# USB_PD.net
KiCad netlist of a schematic drawn in Altium Designer
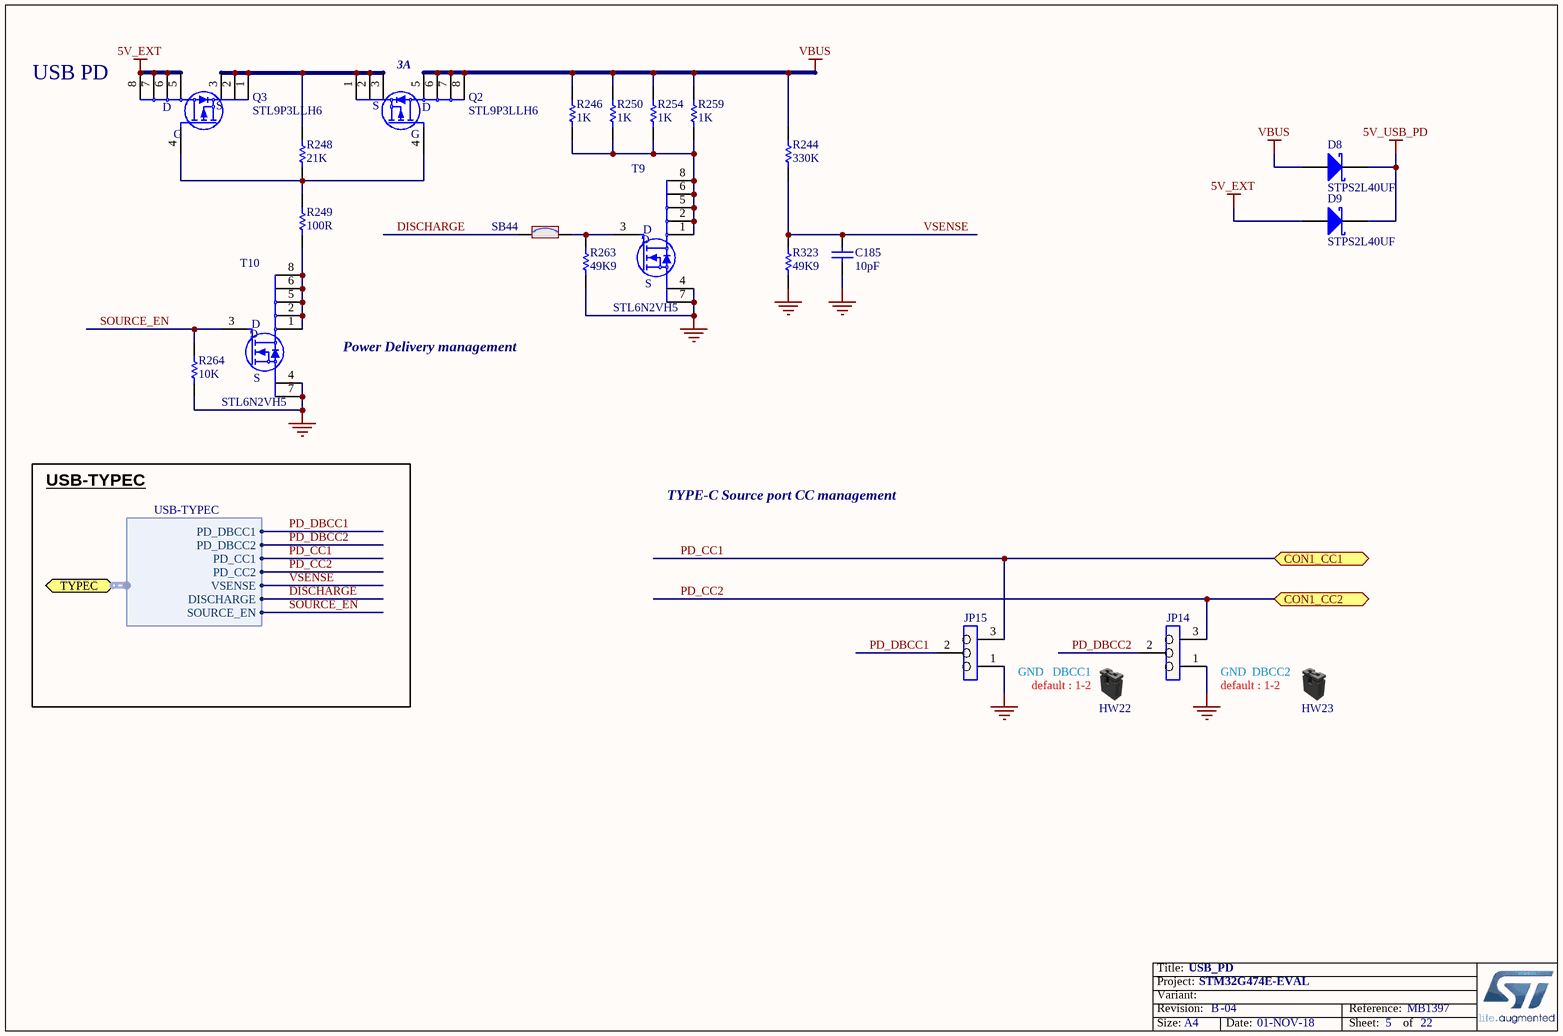
[diagram p0: USB_PD.SchDoc]

(export (version "E")
  (design (tool "Eeschema 10.0.6"))
  (components
    (comp (ref "C185")
      (value "10pF")
      (footprint "C0603")
      (description "Capacitor, MLCC, 10pF, 50V, NPO, 5%, 0603, T=0,8mm")
      (fields
        (field (name "INTERNAL_PART_NUMBER") "MCD-00637")
        (field (name "MANUFACTURER_PART_NUMBER") "CC0603JRNPO9BN100")
        (field (name "PROVIDED_BY") "SUBCO")
      )
      (libsource (lib "MCD_PARTS_database") (part "Capacitor"))
    )
    (comp (ref "D8")
      (value "STPS2L40UF")
      (footprint "DIO_SMB-FLAT_1A_2K")
      (description "Low drop power Schottky rectifier(2A, 40V, 0.34V)")
      (fields
        (field (name "INTERNAL_PART_NUMBER") "MCD-01087")
        (field (name "MANUFACTURER") "STMICROELECTRONICS")
        (field (name "PROVIDED_BY") "SUBCO with ST control")
      )
      (libsource (lib "MCD_PARTS_database") (part "STPS2L40UF"))
    )
    (comp (ref "D9")
      (value "STPS2L40UF")
      (footprint "DIO_SMB-FLAT_1A_2K")
      (description "Low drop power Schottky rectifier(2A, 40V, 0.34V)")
      (fields
        (field (name "INTERNAL_PART_NUMBER") "MCD-01087")
        (field (name "MANUFACTURER") "STMICROELECTRONICS")
        (field (name "PROVIDED_BY") "SUBCO with ST control")
      )
      (libsource (lib "MCD_PARTS_database") (part "STPS2L40UF"))
    )
    (comp (ref "HW22")
      (value "Shunt Black 2.54mm")
      (description "SHUNT 2.54mm BLACK")
      (fields
        (field (name "INTERNAL_PART_NUMBER") "MCD-00043")
        (field (name "MANUFACTURER_PART_NUMBER") "SNT-100-BK-G")
        (field (name "PROVIDED_BY") "SUBCO")
      )
      (libsource (lib "MCD_PARTS_database") (part "Shunt Black 2.54mm"))
    )
    (comp (ref "HW23")
      (value "Shunt Black 2.54mm")
      (description "SHUNT 2.54mm BLACK")
      (fields
        (field (name "INTERNAL_PART_NUMBER") "MCD-00043")
        (field (name "MANUFACTURER_PART_NUMBER") "SNT-100-BK-G")
        (field (name "PROVIDED_BY") "SUBCO")
      )
      (libsource (lib "MCD_PARTS_database") (part "Shunt Black 2.54mm"))
    )
    (comp (ref "JP14")
      (value "Jumper_Header 3x1")
      (footprint "CON_SAMTEC_TSW-103-07-F-S")
      (description "Header, 3x1, 2,54mm, VR, TH, Height 5.84mm/2.54mm")
      (fields
        (field (name "INTERNAL_PART_NUMBER") "MCD-00111")
        (field (name "MANUFACTURER_PART_NUMBER") "TSW-103-07-F-S")
        (field (name "PROVIDED_BY") "SUBCO")
      )
      (libsource (lib "MCD_PARTS_database") (part "Jumper_Header 3x1"))
    )
    (comp (ref "JP15")
      (value "Jumper_Header 3x1")
      (footprint "CON_SAMTEC_TSW-103-07-F-S")
      (description "Header, 3x1, 2,54mm, VR, TH, Height 5.84mm/2.54mm")
      (fields
        (field (name "INTERNAL_PART_NUMBER") "MCD-00111")
        (field (name "MANUFACTURER_PART_NUMBER") "TSW-103-07-F-S")
        (field (name "PROVIDED_BY") "SUBCO")
      )
      (libsource (lib "MCD_PARTS_database") (part "Jumper_Header 3x1"))
    )
    (comp (ref "Q2")
      (value "STL9P3LLH6")
      (footprint "MOS_POWERFLAT_3P3X3P3_P065")
      (description "Power Mosfet, P-channel,VDS -30V,RDS 12mohm typ,ID -9A")
      (fields
        (field (name "INTERNAL_PART_NUMBER") "MCD-01126")
        (field (name "MANUFACTURER") "STMICROELECTRONICS")
        (field (name "PROVIDED_BY") "SUBCO with ST control")
      )
      (libsource (lib "MCD_PARTS_database") (part "STL9P3LLH6"))
    )
    (comp (ref "Q3")
      (value "STL9P3LLH6")
      (footprint "MOS_POWERFLAT_3P3X3P3_P065")
      (description "Power Mosfet, P-channel,VDS -30V,RDS 12mohm typ,ID -9A")
      (fields
        (field (name "INTERNAL_PART_NUMBER") "MCD-01126")
        (field (name "MANUFACTURER") "STMICROELECTRONICS")
        (field (name "PROVIDED_BY") "SUBCO with ST control")
      )
      (libsource (lib "MCD_PARTS_database") (part "STL9P3LLH6"))
    )
    (comp (ref "R244")
      (value "330K")
      (footprint "R0603")
      (description "Resistor,330K,0603,1%,1/10W")
      (fields
        (field (name "INTERNAL_PART_NUMBER") "MCD-00458")
        (field (name "MANUFACTURER_PART_NUMBER") "RC0603FR-07330KL")
        (field (name "PROVIDED_BY") "SUBCO")
      )
      (libsource (lib "MCD_PARTS_database") (part "Resistor"))
    )
    (comp (ref "R246")
      (value "1K")
      (footprint "R0603")
      (description "Resistor,1K,0603,1%,1/10W")
      (fields
        (field (name "INTERNAL_PART_NUMBER") "MCD-00070")
        (field (name "MANUFACTURER_PART_NUMBER") "RC0603FR-071KL")
        (field (name "PROVIDED_BY") "SUBCO")
      )
      (libsource (lib "MCD_PARTS_database") (part "Resistor"))
    )
    (comp (ref "R248")
      (value "21K")
      (footprint "R0603")
      (description "Resistor,21K,0603,1%,1/10W")
      (fields
        (field (name "INTERNAL_PART_NUMBER") "MCD-01189")
        (field (name "MANUFACTURER_PART_NUMBER") "RC0603FR-0721KL")
        (field (name "PROVIDED_BY") "SUBCO")
      )
      (libsource (lib "MCD_PARTS_database") (part "Resistor"))
    )
    (comp (ref "R249")
      (value "100R")
      (footprint "R0603")
      (description "Resistor,100R,0603,1%,1/10W")
      (fields
        (field (name "INTERNAL_PART_NUMBER") "MCD-00224")
        (field (name "MANUFACTURER_PART_NUMBER") "RC0603FR-07100RL")
        (field (name "PROVIDED_BY") "SUBCO")
      )
      (libsource (lib "MCD_PARTS_database") (part "Resistor"))
    )
    (comp (ref "R250")
      (value "1K")
      (footprint "R0603")
      (description "Resistor,1K,0603,1%,1/10W")
      (fields
        (field (name "INTERNAL_PART_NUMBER") "MCD-00070")
        (field (name "MANUFACTURER_PART_NUMBER") "RC0603FR-071KL")
        (field (name "PROVIDED_BY") "SUBCO")
      )
      (libsource (lib "MCD_PARTS_database") (part "Resistor"))
    )
    (comp (ref "R254")
      (value "1K")
      (footprint "R0603")
      (description "Resistor,1K,0603,1%,1/10W")
      (fields
        (field (name "INTERNAL_PART_NUMBER") "MCD-00070")
        (field (name "MANUFACTURER_PART_NUMBER") "RC0603FR-071KL")
        (field (name "PROVIDED_BY") "SUBCO")
      )
      (libsource (lib "MCD_PARTS_database") (part "Resistor"))
    )
    (comp (ref "R259")
      (value "1K")
      (footprint "R0603")
      (description "Resistor,1K,0603,1%,1/10W")
      (fields
        (field (name "INTERNAL_PART_NUMBER") "MCD-00070")
        (field (name "MANUFACTURER_PART_NUMBER") "RC0603FR-071KL")
        (field (name "PROVIDED_BY") "SUBCO")
      )
      (libsource (lib "MCD_PARTS_database") (part "Resistor"))
    )
    (comp (ref "R263")
      (value "49K9")
      (footprint "R0603")
      (description "Resistor,49K9,0603,1%")
      (fields
        (field (name "INTERNAL_PART_NUMBER") "MCD-01171")
        (field (name "MANUFACTURER_PART_NUMBER") "RC0603FR-0749K9L")
        (field (name "PROVIDED_BY") "SUBCO")
      )
      (libsource (lib "MCD_PARTS_database") (part "Resistor"))
    )
    (comp (ref "R264")
      (value "10K")
      (footprint "R0603")
      (description "Resistor,10K,0603,1%,1/10W")
      (fields
        (field (name "INTERNAL_PART_NUMBER") "MCD-00220")
        (field (name "MANUFACTURER_PART_NUMBER") "RC0603FR-0710KL")
        (field (name "PROVIDED_BY") "SUBCO")
      )
      (libsource (lib "MCD_PARTS_database") (part "Resistor"))
    )
    (comp (ref "R323")
      (value "49K9")
      (footprint "R0603")
      (description "Resistor,49K9,0603,1%")
      (fields
        (field (name "INTERNAL_PART_NUMBER") "MCD-01171")
        (field (name "MANUFACTURER_PART_NUMBER") "RC0603FR-0749K9L")
        (field (name "PROVIDED_BY") "SUBCO")
      )
      (libsource (lib "MCD_PARTS_database") (part "Resistor"))
    )
    (comp (ref "SB44")
      (value "SB_ON")
      (footprint "SOLDER-BRIDGE_R0603-0R")
      (description "Solder Bridge ON")
      (fields
        (field (name "INTERNAL_PART_NUMBER") "MCD-00071")
        (field (name "MANUFACTURER_PART_NUMBER") "RC0603JR-070RL")
        (field (name "PROVIDED_BY") "SUBCO")
      )
      (libsource (lib "MCD_PARTS_database") (part "SB_ON"))
    )
    (comp (ref "T9")
      (value "STL6N2VH5")
      (footprint "MOS_POWERFLAT_2X2_P065")
      (description "N-channel 20 V, 0.025 O typ., 6 A STripFET™ V Power MOSFET in a PowerFLAT™ 2x2 package")
      (fields
        (field (name "INTERNAL_PART_NUMBER") "MCD-01028")
        (field (name "MANUFACTURER") "STMICROELECTRONICS")
        (field (name "PROVIDED_BY") "SUBCO with ST control")
      )
      (libsource (lib "MCD_PARTS_database") (part "STL6N2VH5"))
    )
    (comp (ref "T10")
      (value "STL6N2VH5")
      (footprint "MOS_POWERFLAT_2X2_P065")
      (description "N-channel 20 V, 0.025 O typ., 6 A STripFET™ V Power MOSFET in a PowerFLAT™ 2x2 package")
      (fields
        (field (name "INTERNAL_PART_NUMBER") "MCD-01028")
        (field (name "MANUFACTURER") "STMICROELECTRONICS")
        (field (name "PROVIDED_BY") "SUBCO with ST control")
      )
      (libsource (lib "MCD_PARTS_database") (part "STL6N2VH5"))
    )
  )
  (nets
    (net (code "2") (name "/DISCHARGE") (class "Default")
      (node (ref "SB44") (pin "1") (pinfunction "1_1") (pintype "passive"))
    )
    (net (code "3") (name "/PD_CC1") (class "Default")
      (node (ref "JP15") (pin "3") (pinfunction "3_3") (pintype "passive"))
    )
    (net (code "4") (name "/PD_CC2") (class "Default")
      (node (ref "JP14") (pin "3") (pinfunction "3_3") (pintype "passive"))
    )
    (net (code "5") (name "/PD_DBCC1") (class "Default")
      (node (ref "JP15") (pin "2") (pinfunction "2_2") (pintype "passive"))
    )
    (net (code "6") (name "/PD_DBCC2") (class "Default")
      (node (ref "JP14") (pin "2") (pinfunction "2_2") (pintype "passive"))
    )
    (net (code "7") (name "/SOURCE_EN") (class "Default")
      (node (ref "R264") (pin "2") (pinfunction "2_2") (pintype "passive"))
      (node (ref "T10") (pin "3") (pinfunction "G_3") (pintype "passive"))
    )
    (net (code "8") (name "/VSENSE") (class "Default")
      (node (ref "C185") (pin "2") (pinfunction "2_2") (pintype "passive"))
      (node (ref "R244") (pin "1") (pinfunction "1_1") (pintype "passive"))
      (node (ref "R323") (pin "2") (pinfunction "2_2") (pintype "passive"))
    )
    (net (code "10") (name "5V_EXT") (class "Default")
      (node (ref "D9") (pin "1") (pinfunction "A_1") (pintype "passive"))
      (node (ref "Q3") (pin "5") (pinfunction "D_5") (pintype "passive"))
      (node (ref "Q3") (pin "6") (pinfunction "D_6") (pintype "passive"))
      (node (ref "Q3") (pin "7") (pinfunction "D_7") (pintype "passive"))
      (node (ref "Q3") (pin "8") (pinfunction "D_8") (pintype "passive"))
    )
    (net (code "11") (name "5V_USB_PD") (class "Default")
      (node (ref "D8") (pin "2") (pinfunction "K_2") (pintype "passive"))
      (node (ref "D9") (pin "2") (pinfunction "K_2") (pintype "passive"))
    )
    (net (code "12") (name "GND") (class "Default")
      (node (ref "C185") (pin "1") (pinfunction "1_1") (pintype "passive"))
      (node (ref "JP14") (pin "1") (pinfunction "1_1") (pintype "passive"))
      (node (ref "JP15") (pin "1") (pinfunction "1_1") (pintype "passive"))
      (node (ref "R263") (pin "1") (pinfunction "1_1") (pintype "passive"))
      (node (ref "R264") (pin "1") (pinfunction "1_1") (pintype "passive"))
      (node (ref "R323") (pin "1") (pinfunction "1_1") (pintype "passive"))
      (node (ref "T10") (pin "4") (pinfunction "S_4") (pintype "passive"))
      (node (ref "T10") (pin "7") (pinfunction "S_7") (pintype "passive"))
      (node (ref "T9") (pin "4") (pinfunction "S_4") (pintype "passive"))
      (node (ref "T9") (pin "7") (pinfunction "S_7") (pintype "passive"))
    )
    (net (code "13") (name "Net-(Q2-G)") (class "Default")
      (node (ref "Q2") (pin "4") (pinfunction "G_4") (pintype "passive"))
      (node (ref "Q3") (pin "4") (pinfunction "G_4") (pintype "passive"))
      (node (ref "R248") (pin "1") (pinfunction "1_1") (pintype "passive"))
      (node (ref "R249") (pin "2") (pinfunction "2_2") (pintype "passive"))
    )
    (net (code "14") (name "Net-(Q2-S-Pad1)") (class "Default")
      (node (ref "Q2") (pin "1") (pinfunction "S_1") (pintype "passive"))
      (node (ref "Q2") (pin "2") (pinfunction "S_2") (pintype "passive"))
      (node (ref "Q2") (pin "3") (pinfunction "S_3") (pintype "passive"))
      (node (ref "Q3") (pin "1") (pinfunction "S_1") (pintype "passive"))
      (node (ref "Q3") (pin "2") (pinfunction "S_2") (pintype "passive"))
      (node (ref "Q3") (pin "3") (pinfunction "S_3") (pintype "passive"))
      (node (ref "R248") (pin "2") (pinfunction "2_2") (pintype "passive"))
    )
    (net (code "15") (name "Net-(R246-Pad1)") (class "Default")
      (node (ref "R246") (pin "1") (pinfunction "1_1") (pintype "passive"))
      (node (ref "R250") (pin "1") (pinfunction "1_1") (pintype "passive"))
      (node (ref "R254") (pin "1") (pinfunction "1_1") (pintype "passive"))
      (node (ref "R259") (pin "1") (pinfunction "1_1") (pintype "passive"))
      (node (ref "T9") (pin "1") (pinfunction "D_1") (pintype "passive"))
      (node (ref "T9") (pin "2") (pinfunction "D_2") (pintype "passive"))
      (node (ref "T9") (pin "5") (pinfunction "D_5") (pintype "passive"))
      (node (ref "T9") (pin "6") (pinfunction "D_6") (pintype "passive"))
      (node (ref "T9") (pin "8") (pinfunction "D_8") (pintype "passive"))
    )
    (net (code "16") (name "Net-(R249-Pad1)") (class "Default")
      (node (ref "R249") (pin "1") (pinfunction "1_1") (pintype "passive"))
      (node (ref "T10") (pin "1") (pinfunction "D_1") (pintype "passive"))
      (node (ref "T10") (pin "2") (pinfunction "D_2") (pintype "passive"))
      (node (ref "T10") (pin "5") (pinfunction "D_5") (pintype "passive"))
      (node (ref "T10") (pin "6") (pinfunction "D_6") (pintype "passive"))
      (node (ref "T10") (pin "8") (pinfunction "D_8") (pintype "passive"))
    )
    (net (code "17") (name "Net-(T9-G)") (class "Default")
      (node (ref "R263") (pin "2") (pinfunction "2_2") (pintype "passive"))
      (node (ref "SB44") (pin "2") (pinfunction "2_2") (pintype "passive"))
      (node (ref "T9") (pin "3") (pinfunction "G_3") (pintype "passive"))
    )
    (net (code "18") (name "VBUS") (class "Default")
      (node (ref "D8") (pin "1") (pinfunction "A_1") (pintype "passive"))
      (node (ref "Q2") (pin "5") (pinfunction "D_5") (pintype "passive"))
      (node (ref "Q2") (pin "6") (pinfunction "D_6") (pintype "passive"))
      (node (ref "Q2") (pin "7") (pinfunction "D_7") (pintype "passive"))
      (node (ref "Q2") (pin "8") (pinfunction "D_8") (pintype "passive"))
      (node (ref "R244") (pin "2") (pinfunction "2_2") (pintype "passive"))
      (node (ref "R246") (pin "2") (pinfunction "2_2") (pintype "passive"))
      (node (ref "R250") (pin "2") (pinfunction "2_2") (pintype "passive"))
      (node (ref "R254") (pin "2") (pinfunction "2_2") (pintype "passive"))
      (node (ref "R259") (pin "2") (pinfunction "2_2") (pintype "passive"))
    )
  )
)
